# GrblControllerPi.net
KiCad netlist of a schematic drawn in EAGLE
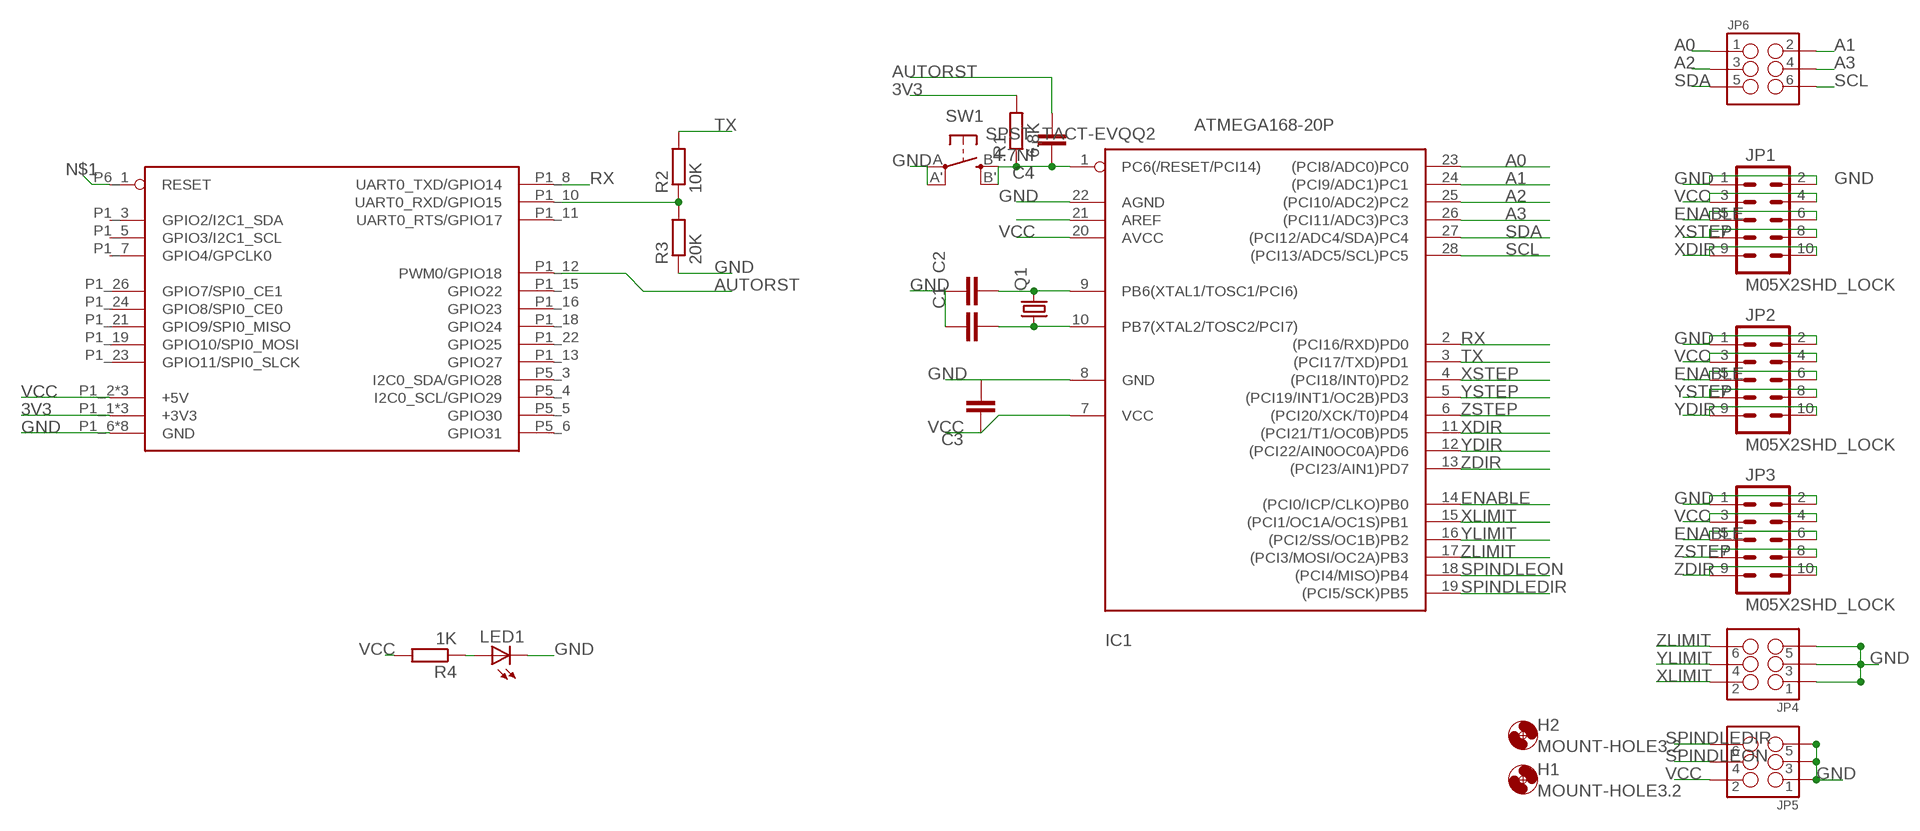
[diagram p0: schematic, sheet 1]

(export (version "E")
  (design (tool "Eeschema 10.0.6"))
  (components
    (comp (ref "C1")
      (value "CAPACITOR_NPOL-1206")
      (footprint "eagle-import:C1206")
      (libsource (lib "eagle-import") (part "CAPACITOR_NPOL-1206"))
    )
    (comp (ref "C2")
      (value "CAPACITOR_NPOL-1206")
      (footprint "eagle-import:C1206")
      (libsource (lib "eagle-import") (part "CAPACITOR_NPOL-1206"))
    )
    (comp (ref "C3")
      (value "CAPACITOR_NPOL-1206")
      (footprint "eagle-import:C1206")
      (libsource (lib "eagle-import") (part "CAPACITOR_NPOL-1206"))
    )
    (comp (ref "C4")
      (value "4.7Nf")
      (footprint "eagle-import:C1206")
      (libsource (lib "eagle-import") (part "CAPACITOR_NPOL-1206"))
    )
    (comp (ref "H1")
      (value "MOUNT-HOLE3.2")
      (footprint "eagle-import:3,2")
      (libsource (lib "eagle-import") (part "MOUNT-HOLE3.2"))
    )
    (comp (ref "H2")
      (value "MOUNT-HOLE3.2")
      (footprint "eagle-import:3,2")
      (libsource (lib "eagle-import") (part "MOUNT-HOLE3.2"))
    )
    (comp (ref "IC1")
      (value "ATMEGA168-20P")
      (footprint "eagle-import:DIL28-3")
      (libsource (lib "eagle-import") (part "ATMEGA168P-20"))
    )
    (comp (ref "JP1")
      (value "M05X2SHD_LOCK")
      (footprint "eagle-import:2X5-SHROUDED_LOCK")
      (libsource (lib "eagle-import") (part "M05X2SHD_LOCK"))
    )
    (comp (ref "JP2")
      (value "M05X2SHD_LOCK")
      (footprint "eagle-import:2X5-SHROUDED_LOCK")
      (libsource (lib "eagle-import") (part "M05X2SHD_LOCK"))
    )
    (comp (ref "JP3")
      (value "M05X2SHD_LOCK")
      (footprint "eagle-import:2X5-SHROUDED_LOCK")
      (libsource (lib "eagle-import") (part "M05X2SHD_LOCK"))
    )
    (comp (ref "JP4")
      (value "M03X2SHROUD")
      (footprint "eagle-import:2X3-SHROUDED")
      (libsource (lib "eagle-import") (part "M03X2SHROUD"))
    )
    (comp (ref "JP5")
      (value "M03X2SHROUD")
      (footprint "eagle-import:2X3-SHROUDED")
      (libsource (lib "eagle-import") (part "M03X2SHROUD"))
    )
    (comp (ref "JP6")
      (value "M03X2SHROUD")
      (footprint "eagle-import:2X3-SHROUDED")
      (libsource (lib "eagle-import") (part "M03X2SHROUD"))
    )
    (comp (ref "LED1")
      (value "LEDCHIPLED_1206")
      (footprint "eagle-import:CHIPLED_1206")
      (libsource (lib "eagle-import") (part "LEDCHIPLED_1206"))
    )
    (comp (ref "Q1")
      (value "CRYSTALHC49UP")
      (footprint "eagle-import:HC49UP")
      (libsource (lib "eagle-import") (part "CRYSTALHC49UP"))
    )
    (comp (ref "R1")
      (value "6.8K")
      (footprint "eagle-import:R1206")
      (libsource (lib "eagle-import") (part "RESISTOR-1206"))
    )
    (comp (ref "R2")
      (value "10K")
      (footprint "eagle-import:R1206")
      (libsource (lib "eagle-import") (part "RESISTOR-1206"))
    )
    (comp (ref "R3")
      (value "20K")
      (footprint "eagle-import:R1206")
      (libsource (lib "eagle-import") (part "RESISTOR-1206"))
    )
    (comp (ref "R4")
      (value "1K")
      (footprint "eagle-import:R1206")
      (libsource (lib "eagle-import") (part "RESISTOR-1206"))
    )
    (comp (ref "SW1")
      (value "SPST_TACT-EVQQ2")
      (footprint "eagle-import:EVQ-Q2")
      (libsource (lib "eagle-import") (part "SPST_TACT-EVQQ2"))
    )
    (comp (ref "U$1")
      (value "RPI-B-V2SHIELD")
      (footprint "eagle-import:RPI-B-V2-SHIELD")
      (libsource (lib "eagle-import") (part "RPI-B-V2SHIELD"))
    )
  )
  (nets
    (net (code "1") (name "/3V3") (class "Default")
      (node (ref "R1") (pin "2") (pinfunction "2_2") (pintype "passive"))
      (node (ref "U$1") (pin "P1_1") (pinfunction "+3V3_P1_1") (pintype "power_in"))
      (node (ref "U$1") (pin "P1_17") (pinfunction "+3V3_P1_17") (pintype "power_in"))
      (node (ref "U$1") (pin "P5_2") (pinfunction "+3V3_P5_2") (pintype "power_in"))
    )
    (net (code "2") (name "/A0") (class "Default")
      (node (ref "IC1") (pin "23") (pinfunction "(PCI8/ADC0)PC0_23") (pintype "bidirectional"))
      (node (ref "JP6") (pin "1") (pinfunction "1_1") (pintype "bidirectional"))
    )
    (net (code "3") (name "/A1") (class "Default")
      (node (ref "IC1") (pin "24") (pinfunction "(PCI9/ADC1)PC1_24") (pintype "bidirectional"))
      (node (ref "JP6") (pin "2") (pinfunction "2_2") (pintype "bidirectional"))
    )
    (net (code "4") (name "/A2") (class "Default")
      (node (ref "IC1") (pin "25") (pinfunction "(PCI10/ADC2)PC2_25") (pintype "bidirectional"))
      (node (ref "JP6") (pin "3") (pinfunction "3_3") (pintype "bidirectional"))
    )
    (net (code "5") (name "/A3") (class "Default")
      (node (ref "IC1") (pin "26") (pinfunction "(PCI11/ADC3)PC3_26") (pintype "bidirectional"))
      (node (ref "JP6") (pin "4") (pinfunction "4_4") (pintype "bidirectional"))
    )
    (net (code "6") (name "/AUTORST") (class "Default")
      (node (ref "C4") (pin "2") (pinfunction "2_2") (pintype "passive"))
      (node (ref "U$1") (pin "P1_12") (pinfunction "PWM0/GPIO18_P1_12") (pintype "bidirectional"))
    )
    (net (code "7") (name "/ENABLE") (class "Default")
      (node (ref "IC1") (pin "14") (pinfunction "(PCI0/ICP/CLKO)PB0_14") (pintype "bidirectional"))
      (node (ref "JP1") (pin "5") (pinfunction "5_5") (pintype "passive"))
      (node (ref "JP1") (pin "6") (pinfunction "6_6") (pintype "passive"))
      (node (ref "JP2") (pin "5") (pinfunction "5_5") (pintype "passive"))
      (node (ref "JP2") (pin "6") (pinfunction "6_6") (pintype "passive"))
      (node (ref "JP3") (pin "5") (pinfunction "5_5") (pintype "passive"))
      (node (ref "JP3") (pin "6") (pinfunction "6_6") (pintype "passive"))
    )
    (net (code "8") (name "/GND") (class "Default")
      (node (ref "C1") (pin "1") (pinfunction "1_1") (pintype "passive"))
      (node (ref "C2") (pin "1") (pinfunction "1_1") (pintype "passive"))
      (node (ref "C3") (pin "2") (pinfunction "2_2") (pintype "passive"))
      (node (ref "IC1") (pin "22") (pinfunction "AGND_22") (pintype "bidirectional"))
      (node (ref "IC1") (pin "8") (pinfunction "GND_8") (pintype "bidirectional"))
      (node (ref "JP1") (pin "1") (pinfunction "1_1") (pintype "passive"))
      (node (ref "JP1") (pin "2") (pinfunction "2_2") (pintype "passive"))
      (node (ref "JP2") (pin "1") (pinfunction "1_1") (pintype "passive"))
      (node (ref "JP2") (pin "2") (pinfunction "2_2") (pintype "passive"))
      (node (ref "JP3") (pin "1") (pinfunction "1_1") (pintype "passive"))
      (node (ref "JP3") (pin "2") (pinfunction "2_2") (pintype "passive"))
      (node (ref "JP4") (pin "1") (pinfunction "1_1") (pintype "bidirectional"))
      (node (ref "JP4") (pin "3") (pinfunction "3_3") (pintype "bidirectional"))
      (node (ref "JP4") (pin "5") (pinfunction "5_5") (pintype "bidirectional"))
      (node (ref "JP5") (pin "1") (pinfunction "1_1") (pintype "bidirectional"))
      (node (ref "JP5") (pin "3") (pinfunction "3_3") (pintype "bidirectional"))
      (node (ref "JP5") (pin "5") (pinfunction "5_5") (pintype "bidirectional"))
      (node (ref "LED1") (pin "C") (pinfunction "C_C") (pintype "passive"))
      (node (ref "R3") (pin "1") (pinfunction "1_1") (pintype "passive"))
      (node (ref "SW1") (pin "A") (pinfunction "P_A") (pintype "passive"))
      (node (ref "SW1") (pin "A'") (pinfunction "P1_A'") (pintype "passive"))
      (node (ref "U$1") (pin "P1_14") (pinfunction "GND_P1_14") (pintype "power_in"))
      (node (ref "U$1") (pin "P1_20") (pinfunction "GND_P1_20") (pintype "power_in"))
      (node (ref "U$1") (pin "P1_25") (pinfunction "GND_P1_25") (pintype "power_in"))
      (node (ref "U$1") (pin "P1_6") (pinfunction "GND_P1_6") (pintype "power_in"))
      (node (ref "U$1") (pin "P1_9") (pinfunction "GND_P1_9") (pintype "power_in"))
      (node (ref "U$1") (pin "P5_7") (pinfunction "GND_P5_7") (pintype "power_in"))
      (node (ref "U$1") (pin "P5_8") (pinfunction "GND_P5_8") (pintype "power_in"))
      (node (ref "U$1") (pin "P6_2") (pinfunction "GND_P6_2") (pintype "power_in"))
    )
    (net (code "9") (name "/GPIO30") (class "Default")
      (node (ref "U$1") (pin "P5_5") (pinfunction "GPIO30_P5_5") (pintype "power_in"))
    )
    (net (code "10") (name "/GPIO31") (class "Default")
      (node (ref "U$1") (pin "P5_6") (pinfunction "GPIO31_P5_6") (pintype "power_in"))
    )
    (net (code "11") (name "/I2C0_SCL{slash}GPIO29") (class "Default")
      (node (ref "U$1") (pin "P5_4") (pinfunction "I2C0_SCL/GPIO29_P5_4") (pintype "power_in"))
    )
    (net (code "12") (name "/I2C0_SDA{slash}GPIO28") (class "Default")
      (node (ref "U$1") (pin "P5_3") (pinfunction "I2C0_SDA/GPIO28_P5_3") (pintype "power_in"))
    )
    (net (code "13") (name "/N$1") (class "Default")
      (node (ref "U$1") (pin "P6_1") (pinfunction "RESET_P6_1") (pintype "power_in"))
    )
    (net (code "14") (name "/RX") (class "Default")
      (node (ref "IC1") (pin "2") (pinfunction "(PCI16/RXD)PD0_2") (pintype "bidirectional"))
      (node (ref "U$1") (pin "P1_8") (pinfunction "UART0_TXD/GPIO14_P1_8") (pintype "bidirectional"))
    )
    (net (code "15") (name "/SCL") (class "Default")
      (node (ref "IC1") (pin "28") (pinfunction "(PCI13/ADC5/SCL)PC5_28") (pintype "bidirectional"))
      (node (ref "JP6") (pin "6") (pinfunction "6_6") (pintype "bidirectional"))
    )
    (net (code "16") (name "/SDA") (class "Default")
      (node (ref "IC1") (pin "27") (pinfunction "(PCI12/ADC4/SDA)PC4_27") (pintype "bidirectional"))
      (node (ref "JP6") (pin "5") (pinfunction "5_5") (pintype "bidirectional"))
    )
    (net (code "17") (name "/SPINDLEDIR") (class "Default")
      (node (ref "IC1") (pin "19") (pinfunction "(PCI5/SCK)PB5_19") (pintype "bidirectional"))
      (node (ref "JP5") (pin "6") (pinfunction "6_6") (pintype "bidirectional"))
    )
    (net (code "18") (name "/SPINDLEON") (class "Default")
      (node (ref "IC1") (pin "18") (pinfunction "(PCI4/MISO)PB4_18") (pintype "bidirectional"))
      (node (ref "JP5") (pin "4") (pinfunction "4_4") (pintype "bidirectional"))
    )
    (net (code "19") (name "/TX") (class "Default")
      (node (ref "IC1") (pin "3") (pinfunction "(PCI17/TXD)PD1_3") (pintype "bidirectional"))
      (node (ref "R2") (pin "2") (pinfunction "2_2") (pintype "passive"))
    )
    (net (code "20") (name "/VCC") (class "Default")
      (node (ref "C3") (pin "1") (pinfunction "1_1") (pintype "passive"))
      (node (ref "IC1") (pin "20") (pinfunction "AVCC_20") (pintype "bidirectional"))
      (node (ref "IC1") (pin "7") (pinfunction "VCC_7") (pintype "bidirectional"))
      (node (ref "JP1") (pin "3") (pinfunction "3_3") (pintype "passive"))
      (node (ref "JP1") (pin "4") (pinfunction "4_4") (pintype "passive"))
      (node (ref "JP2") (pin "3") (pinfunction "3_3") (pintype "passive"))
      (node (ref "JP2") (pin "4") (pinfunction "4_4") (pintype "passive"))
      (node (ref "JP3") (pin "3") (pinfunction "3_3") (pintype "passive"))
      (node (ref "JP3") (pin "4") (pinfunction "4_4") (pintype "passive"))
      (node (ref "JP5") (pin "2") (pinfunction "2_2") (pintype "bidirectional"))
      (node (ref "R4") (pin "2") (pinfunction "2_2") (pintype "passive"))
      (node (ref "U$1") (pin "P1_2") (pinfunction "+5V_P1_2") (pintype "power_in"))
      (node (ref "U$1") (pin "P1_4") (pinfunction "+5V_P1_4") (pintype "power_in"))
      (node (ref "U$1") (pin "P5_1") (pinfunction "+5V_P5_1") (pintype "power_in"))
    )
    (net (code "21") (name "/XDIR") (class "Default")
      (node (ref "IC1") (pin "11") (pinfunction "(PCI21/T1/OC0B)PD5_11") (pintype "bidirectional"))
      (node (ref "JP1") (pin "10") (pinfunction "10_10") (pintype "passive"))
      (node (ref "JP1") (pin "9") (pinfunction "9_9") (pintype "passive"))
    )
    (net (code "22") (name "/XLIMIT") (class "Default")
      (node (ref "IC1") (pin "15") (pinfunction "(PCI1/OC1A/OC1S)PB1_15") (pintype "bidirectional"))
      (node (ref "JP4") (pin "2") (pinfunction "2_2") (pintype "bidirectional"))
    )
    (net (code "23") (name "/XSTEP") (class "Default")
      (node (ref "IC1") (pin "4") (pinfunction "(PCI18/INT0)PD2_4") (pintype "bidirectional"))
      (node (ref "JP1") (pin "7") (pinfunction "7_7") (pintype "passive"))
      (node (ref "JP1") (pin "8") (pinfunction "8_8") (pintype "passive"))
    )
    (net (code "24") (name "/YDIR") (class "Default")
      (node (ref "IC1") (pin "12") (pinfunction "(PCI22/AIN0OC0A)PD6_12") (pintype "bidirectional"))
      (node (ref "JP2") (pin "10") (pinfunction "10_10") (pintype "passive"))
      (node (ref "JP2") (pin "9") (pinfunction "9_9") (pintype "passive"))
    )
    (net (code "25") (name "/YLIMIT") (class "Default")
      (node (ref "IC1") (pin "16") (pinfunction "(PCI2/SS/OC1B)PB2_16") (pintype "bidirectional"))
      (node (ref "JP4") (pin "4") (pinfunction "4_4") (pintype "bidirectional"))
    )
    (net (code "26") (name "/YSTEP") (class "Default")
      (node (ref "IC1") (pin "5") (pinfunction "(PCI19/INT1/OC2B)PD3_5") (pintype "bidirectional"))
      (node (ref "JP2") (pin "7") (pinfunction "7_7") (pintype "passive"))
      (node (ref "JP2") (pin "8") (pinfunction "8_8") (pintype "passive"))
    )
    (net (code "27") (name "/ZDIR") (class "Default")
      (node (ref "IC1") (pin "13") (pinfunction "(PCI23/AIN1)PD7_13") (pintype "bidirectional"))
      (node (ref "JP3") (pin "10") (pinfunction "10_10") (pintype "passive"))
      (node (ref "JP3") (pin "9") (pinfunction "9_9") (pintype "passive"))
    )
    (net (code "28") (name "/ZLIMIT") (class "Default")
      (node (ref "IC1") (pin "17") (pinfunction "(PCI3/MOSI/OC2A)PB3_17") (pintype "bidirectional"))
      (node (ref "JP4") (pin "6") (pinfunction "6_6") (pintype "bidirectional"))
    )
    (net (code "29") (name "/ZSTEP") (class "Default")
      (node (ref "IC1") (pin "6") (pinfunction "(PCI20/XCK/T0)PD4_6") (pintype "bidirectional"))
      (node (ref "JP3") (pin "7") (pinfunction "7_7") (pintype "passive"))
      (node (ref "JP3") (pin "8") (pinfunction "8_8") (pintype "passive"))
    )
    (net (code "30") (name "Net-(IC1-PB6(XTAL1{slash}TOSC1{slash}PCI6))") (class "Default")
      (node (ref "C2") (pin "2") (pinfunction "2_2") (pintype "passive"))
      (node (ref "IC1") (pin "9") (pinfunction "PB6(XTAL1/TOSC1/PCI6)_9") (pintype "bidirectional"))
      (node (ref "Q1") (pin "2") (pinfunction "2_2") (pintype "passive"))
    )
    (net (code "31") (name "Net-(IC1-PB7(XTAL2{slash}TOSC2{slash}PCI7))") (class "Default")
      (node (ref "C1") (pin "2") (pinfunction "2_2") (pintype "passive"))
      (node (ref "IC1") (pin "10") (pinfunction "PB7(XTAL2/TOSC2/PCI7)_10") (pintype "bidirectional"))
      (node (ref "Q1") (pin "1") (pinfunction "1_1") (pintype "passive"))
    )
    (net (code "32") (name "Net-(IC1-PC6({slash}RESET{slash}PCI14))") (class "Default")
      (node (ref "C4") (pin "1") (pinfunction "1_1") (pintype "passive"))
      (node (ref "IC1") (pin "1") (pinfunction "PC6(/RESET/PCI14)_1") (pintype "bidirectional"))
      (node (ref "R1") (pin "1") (pinfunction "1_1") (pintype "passive"))
      (node (ref "SW1") (pin "B") (pinfunction "S_B") (pintype "passive"))
      (node (ref "SW1") (pin "B'") (pinfunction "S1_B'") (pintype "passive"))
    )
    (net (code "33") (name "Net-(LED1-PadA)") (class "Default")
      (node (ref "LED1") (pin "A") (pinfunction "A_A") (pintype "passive"))
      (node (ref "R4") (pin "1") (pinfunction "1_1") (pintype "passive"))
    )
    (net (code "34") (name "Net-(U$1-UART0_RXD{slash}GPIO15)") (class "Default")
      (node (ref "R2") (pin "1") (pinfunction "1_1") (pintype "passive"))
      (node (ref "R3") (pin "2") (pinfunction "2_2") (pintype "passive"))
      (node (ref "U$1") (pin "P1_10") (pinfunction "UART0_RXD/GPIO15_P1_10") (pintype "bidirectional"))
    )
    (net (code "35") (name "unconnected-(IC1-AREF-Pad21)") (class "Default")
      (node (ref "IC1") (pin "21") (pinfunction "AREF_21") (pintype "bidirectional"))
    )
    (net (code "36") (name "unconnected-(U$1-GPIO2{slash}I2C1_SDA-PadP1_3)") (class "Default")
      (node (ref "U$1") (pin "P1_3") (pinfunction "GPIO2/I2C1_SDA_P1_3") (pintype "bidirectional"))
    )
    (net (code "37") (name "unconnected-(U$1-GPIO3{slash}I2C1_SCL-PadP1_5)") (class "Default")
      (node (ref "U$1") (pin "P1_5") (pinfunction "GPIO3/I2C1_SCL_P1_5") (pintype "bidirectional"))
    )
    (net (code "38") (name "unconnected-(U$1-GPIO4{slash}GPCLK0-PadP1_7)") (class "Default")
      (node (ref "U$1") (pin "P1_7") (pinfunction "GPIO4/GPCLK0_P1_7") (pintype "bidirectional"))
    )
    (net (code "39") (name "unconnected-(U$1-GPIO7{slash}SPI0_CE1-PadP1_26)") (class "Default")
      (node (ref "U$1") (pin "P1_26") (pinfunction "GPIO7/SPI0_CE1_P1_26") (pintype "bidirectional"))
    )
    (net (code "40") (name "unconnected-(U$1-GPIO8{slash}SPI0_CE0-PadP1_24)") (class "Default")
      (node (ref "U$1") (pin "P1_24") (pinfunction "GPIO8/SPI0_CE0_P1_24") (pintype "bidirectional"))
    )
    (net (code "41") (name "unconnected-(U$1-GPIO9{slash}SPI0_MISO-PadP1_21)") (class "Default")
      (node (ref "U$1") (pin "P1_21") (pinfunction "GPIO9/SPI0_MISO_P1_21") (pintype "bidirectional"))
    )
    (net (code "42") (name "unconnected-(U$1-GPIO10{slash}SPI0_MOSI-PadP1_19)") (class "Default")
      (node (ref "U$1") (pin "P1_19") (pinfunction "GPIO10/SPI0_MOSI_P1_19") (pintype "bidirectional"))
    )
    (net (code "43") (name "unconnected-(U$1-GPIO11{slash}SPI0_SLCK-PadP1_23)") (class "Default")
      (node (ref "U$1") (pin "P1_23") (pinfunction "GPIO11/SPI0_SLCK_P1_23") (pintype "bidirectional"))
    )
    (net (code "44") (name "unconnected-(U$1-GPIO22-PadP1_15)") (class "Default")
      (node (ref "U$1") (pin "P1_15") (pinfunction "GPIO22_P1_15") (pintype "bidirectional"))
    )
    (net (code "45") (name "unconnected-(U$1-GPIO23-PadP1_16)") (class "Default")
      (node (ref "U$1") (pin "P1_16") (pinfunction "GPIO23_P1_16") (pintype "bidirectional"))
    )
    (net (code "46") (name "unconnected-(U$1-GPIO24-PadP1_18)") (class "Default")
      (node (ref "U$1") (pin "P1_18") (pinfunction "GPIO24_P1_18") (pintype "bidirectional"))
    )
    (net (code "47") (name "unconnected-(U$1-GPIO25-PadP1_22)") (class "Default")
      (node (ref "U$1") (pin "P1_22") (pinfunction "GPIO25_P1_22") (pintype "bidirectional"))
    )
    (net (code "48") (name "unconnected-(U$1-GPIO27-PadP1_13)") (class "Default")
      (node (ref "U$1") (pin "P1_13") (pinfunction "GPIO27_P1_13") (pintype "bidirectional"))
    )
    (net (code "49") (name "unconnected-(U$1-UART0_RTS{slash}GPIO17-PadP1_11)") (class "Default")
      (node (ref "U$1") (pin "P1_11") (pinfunction "UART0_RTS/GPIO17_P1_11") (pintype "bidirectional"))
    )
  )
)
